# 1s.net
KiCad netlist of a schematic drawn in EAGLE
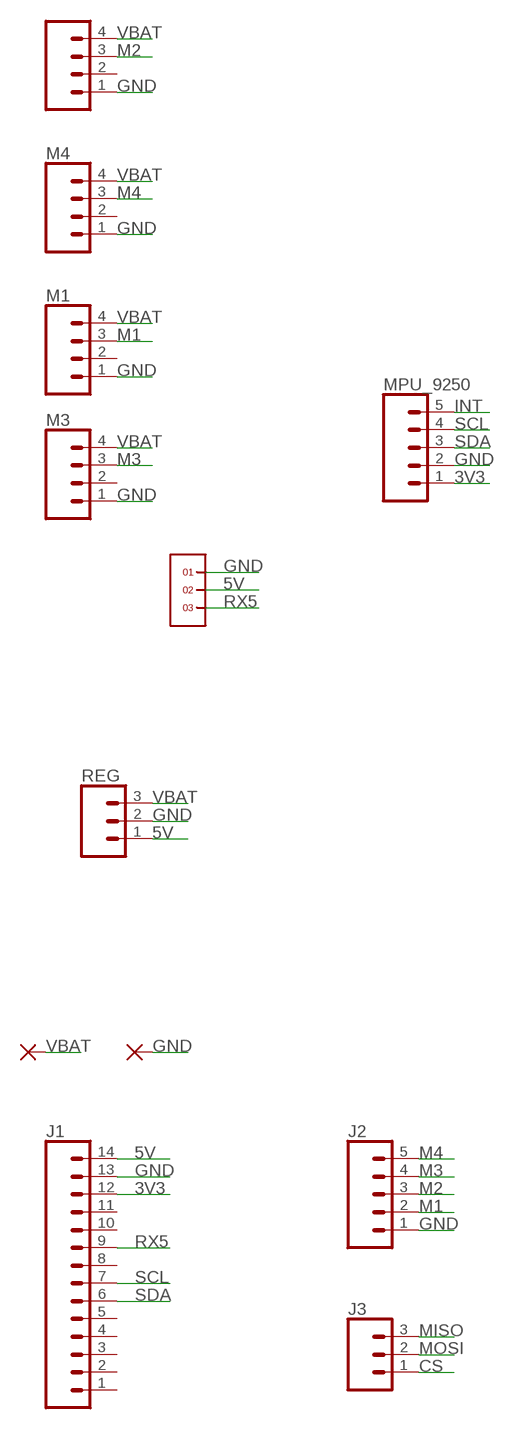
[diagram p0: schematic, sheet 1]

(export (version "E")
  (design (tool "Eeschema 10.0.6"))
  (components
    (comp (ref "GND")
      (value "SMD5")
      (footprint "eagle-import:SMD2,54-5,08")
      (libsource (lib "eagle-import") (part "SMD5"))
    )
    (comp (ref "J1")
      (value "CONN_14NO_SILK")
      (footprint "eagle-import:1X14_NO_SILK")
      (libsource (lib "eagle-import") (part "CONN_14NO_SILK"))
    )
    (comp (ref "J2")
      (value "CONN_05NO_SILK")
      (footprint "eagle-import:1X05_NO_SILK")
      (libsource (lib "eagle-import") (part "CONN_05NO_SILK"))
    )
    (comp (ref "J3")
      (value "CONN_031X03_NO_SILK")
      (footprint "eagle-import:1X03_NO_SILK")
      (libsource (lib "eagle-import") (part "CONN_031X03_NO_SILK"))
    )
    (comp (ref "M1")
      (value "CONN_041X04_NO_SILK")
      (footprint "eagle-import:1X04_NO_SILK")
      (libsource (lib "eagle-import") (part "CONN_041X04_NO_SILK"))
    )
    (comp (ref "M2")
      (value "CONN_041X04_NO_SILK")
      (footprint "eagle-import:1X04_NO_SILK")
      (libsource (lib "eagle-import") (part "CONN_041X04_NO_SILK"))
    )
    (comp (ref "M3")
      (value "CONN_041X04_NO_SILK")
      (footprint "eagle-import:1X04_NO_SILK")
      (libsource (lib "eagle-import") (part "CONN_041X04_NO_SILK"))
    )
    (comp (ref "M4")
      (value "CONN_041X04_NO_SILK")
      (footprint "eagle-import:1X04_NO_SILK")
      (libsource (lib "eagle-import") (part "CONN_041X04_NO_SILK"))
    )
    (comp (ref "MPU_9250")
      (value "CONN_05NO_SILK")
      (footprint "eagle-import:1X05_NO_SILK")
      (libsource (lib "eagle-import") (part "CONN_05NO_SILK"))
    )
    (comp (ref "REG")
      (value "CONN_031X03_NO_SILK")
      (footprint "eagle-import:1X03_NO_SILK")
      (libsource (lib "eagle-import") (part "CONN_031X03_NO_SILK"))
    )
    (comp (ref "SBUS_RX")
      (value "1X3")
      (footprint "eagle-import:1X3")
      (libsource (lib "eagle-import") (part "1X3"))
    )
    (comp (ref "VBAT")
      (value "SMD5")
      (footprint "eagle-import:SMD2,54-5,08")
      (libsource (lib "eagle-import") (part "SMD5"))
    )
  )
  (nets
    (net (code "1") (name "/3V3") (class "Default")
      (node (ref "J1") (pin "12") (pinfunction "12_12") (pintype "passive"))
      (node (ref "MPU_9250") (pin "1") (pinfunction "1_1") (pintype "passive"))
    )
    (net (code "2") (name "/5V") (class "Default")
      (node (ref "J1") (pin "14") (pinfunction "14_14") (pintype "passive"))
      (node (ref "REG") (pin "1") (pinfunction "1_1") (pintype "passive"))
      (node (ref "SBUS_RX") (pin "2") (pinfunction "2_2") (pintype "bidirectional"))
    )
    (net (code "3") (name "/CS") (class "Default")
      (node (ref "J3") (pin "1") (pinfunction "1_1") (pintype "passive"))
    )
    (net (code "4") (name "/GND") (class "Default")
      (node (ref "GND") (pin "1") (pinfunction "P_1") (pintype "passive"))
      (node (ref "J1") (pin "13") (pinfunction "13_13") (pintype "passive"))
      (node (ref "J2") (pin "1") (pinfunction "1_1") (pintype "passive"))
      (node (ref "M1") (pin "1") (pinfunction "1_1") (pintype "passive"))
      (node (ref "M2") (pin "1") (pinfunction "1_1") (pintype "passive"))
      (node (ref "M3") (pin "1") (pinfunction "1_1") (pintype "passive"))
      (node (ref "M4") (pin "1") (pinfunction "1_1") (pintype "passive"))
      (node (ref "MPU_9250") (pin "2") (pinfunction "2_2") (pintype "passive"))
      (node (ref "REG") (pin "2") (pinfunction "2_2") (pintype "passive"))
      (node (ref "SBUS_RX") (pin "1") (pinfunction "1_1") (pintype "bidirectional"))
    )
    (net (code "5") (name "/INT") (class "Default")
      (node (ref "MPU_9250") (pin "5") (pinfunction "5_5") (pintype "passive"))
    )
    (net (code "6") (name "/M1") (class "Default")
      (node (ref "J2") (pin "2") (pinfunction "2_2") (pintype "passive"))
      (node (ref "M1") (pin "3") (pinfunction "3_3") (pintype "passive"))
    )
    (net (code "7") (name "/M2") (class "Default")
      (node (ref "J2") (pin "3") (pinfunction "3_3") (pintype "passive"))
      (node (ref "M2") (pin "3") (pinfunction "3_3") (pintype "passive"))
    )
    (net (code "8") (name "/M3") (class "Default")
      (node (ref "J2") (pin "4") (pinfunction "4_4") (pintype "passive"))
      (node (ref "M3") (pin "3") (pinfunction "3_3") (pintype "passive"))
    )
    (net (code "9") (name "/M4") (class "Default")
      (node (ref "J2") (pin "5") (pinfunction "5_5") (pintype "passive"))
      (node (ref "M4") (pin "3") (pinfunction "3_3") (pintype "passive"))
    )
    (net (code "10") (name "/MISO") (class "Default")
      (node (ref "J3") (pin "3") (pinfunction "3_3") (pintype "passive"))
    )
    (net (code "11") (name "/MOSI") (class "Default")
      (node (ref "J3") (pin "2") (pinfunction "2_2") (pintype "passive"))
    )
    (net (code "12") (name "/RX5") (class "Default")
      (node (ref "J1") (pin "9") (pinfunction "9_9") (pintype "passive"))
      (node (ref "SBUS_RX") (pin "3") (pinfunction "3_3") (pintype "bidirectional"))
    )
    (net (code "13") (name "/SCL") (class "Default")
      (node (ref "J1") (pin "7") (pinfunction "7_7") (pintype "passive"))
      (node (ref "MPU_9250") (pin "4") (pinfunction "4_4") (pintype "passive"))
    )
    (net (code "14") (name "/SDA") (class "Default")
      (node (ref "J1") (pin "6") (pinfunction "6_6") (pintype "passive"))
      (node (ref "MPU_9250") (pin "3") (pinfunction "3_3") (pintype "passive"))
    )
    (net (code "15") (name "/VBAT") (class "Default")
      (node (ref "M1") (pin "4") (pinfunction "4_4") (pintype "passive"))
      (node (ref "M2") (pin "4") (pinfunction "4_4") (pintype "passive"))
      (node (ref "M3") (pin "4") (pinfunction "4_4") (pintype "passive"))
      (node (ref "M4") (pin "4") (pinfunction "4_4") (pintype "passive"))
      (node (ref "REG") (pin "3") (pinfunction "3_3") (pintype "passive"))
      (node (ref "VBAT") (pin "1") (pinfunction "P_1") (pintype "passive"))
    )
    (net (code "16") (name "unconnected-(J1-Pad1)") (class "Default")
      (node (ref "J1") (pin "1") (pinfunction "1_1") (pintype "passive"))
    )
    (net (code "17") (name "unconnected-(J1-Pad2)") (class "Default")
      (node (ref "J1") (pin "2") (pinfunction "2_2") (pintype "passive"))
    )
    (net (code "18") (name "unconnected-(J1-Pad3)") (class "Default")
      (node (ref "J1") (pin "3") (pinfunction "3_3") (pintype "passive"))
    )
    (net (code "19") (name "unconnected-(J1-Pad4)") (class "Default")
      (node (ref "J1") (pin "4") (pinfunction "4_4") (pintype "passive"))
    )
    (net (code "20") (name "unconnected-(J1-Pad5)") (class "Default")
      (node (ref "J1") (pin "5") (pinfunction "5_5") (pintype "passive"))
    )
    (net (code "21") (name "unconnected-(J1-Pad8)") (class "Default")
      (node (ref "J1") (pin "8") (pinfunction "8_8") (pintype "passive"))
    )
    (net (code "22") (name "unconnected-(J1-Pad10)") (class "Default")
      (node (ref "J1") (pin "10") (pinfunction "10_10") (pintype "passive"))
    )
    (net (code "23") (name "unconnected-(J1-Pad11)") (class "Default")
      (node (ref "J1") (pin "11") (pinfunction "11_11") (pintype "passive"))
    )
    (net (code "24") (name "unconnected-(M1-Pad2)") (class "Default")
      (node (ref "M1") (pin "2") (pinfunction "2_2") (pintype "passive"))
    )
    (net (code "25") (name "unconnected-(M2-Pad2)") (class "Default")
      (node (ref "M2") (pin "2") (pinfunction "2_2") (pintype "passive"))
    )
    (net (code "26") (name "unconnected-(M3-Pad2)") (class "Default")
      (node (ref "M3") (pin "2") (pinfunction "2_2") (pintype "passive"))
    )
    (net (code "27") (name "unconnected-(M4-Pad2)") (class "Default")
      (node (ref "M4") (pin "2") (pinfunction "2_2") (pintype "passive"))
    )
  )
)
